# Task2.net
KiCad netlist of a schematic drawn in Altium Designer
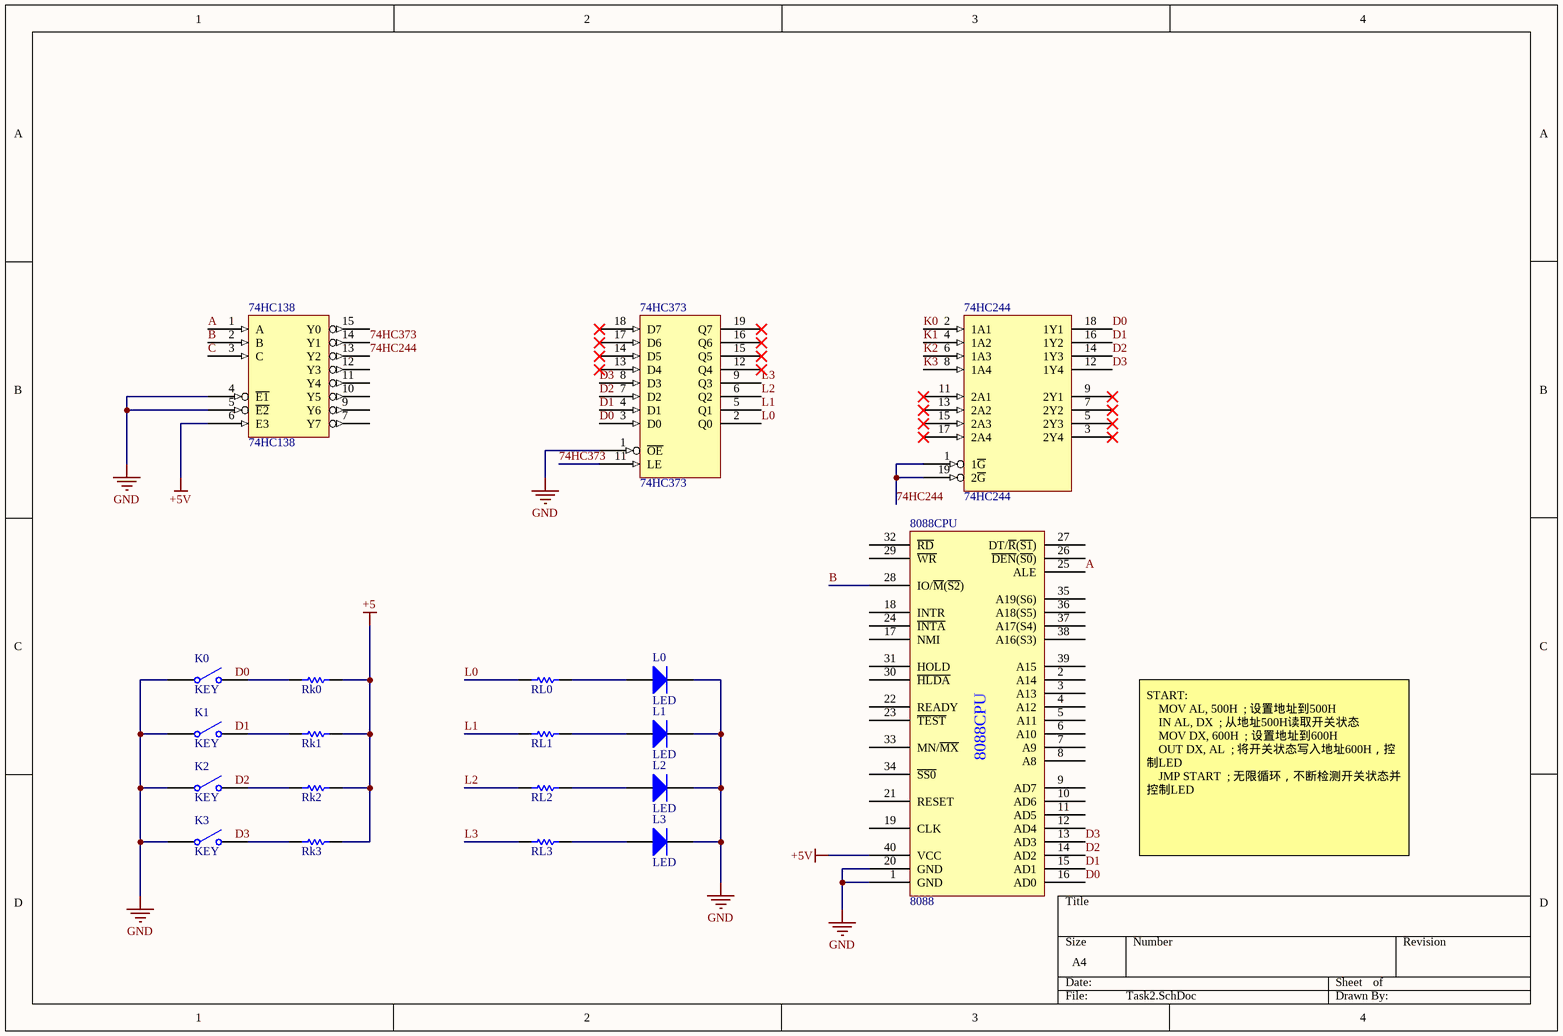
[diagram p0: Task2.SchDoc]

(export (version "E")
  (design (tool "Eeschema 10.0.6"))
  (components
    (comp (ref "74HC138") (value "74HC138") (libsource (lib "BusAndInterfaceDesign") (part "74HC138")))
    (comp (ref "74HC244") (value "74HC244") (libsource (lib "BusAndInterfaceDesign") (part "74HC244")))
    (comp (ref "74HC373") (value "74HC373") (libsource (lib "BusAndInterfaceDesign") (part "74HC373")))
    (comp (ref "8088CPU") (value "8088") (libsource (lib "BusAndInterfaceDesign") (part "8088")))
    (comp (ref "K0") (value "KEY") (libsource (lib "BusAndInterfaceDesign") (part "KEY")))
    (comp (ref "K1") (value "KEY") (libsource (lib "BusAndInterfaceDesign") (part "KEY")))
    (comp (ref "K2") (value "KEY") (libsource (lib "BusAndInterfaceDesign") (part "KEY")))
    (comp (ref "K3") (value "KEY") (libsource (lib "BusAndInterfaceDesign") (part "KEY")))
    (comp (ref "L0") (value "LED") (libsource (lib "BusAndInterfaceDesign") (part "LED")))
    (comp (ref "L1") (value "LED") (libsource (lib "BusAndInterfaceDesign") (part "LED")))
    (comp (ref "L2") (value "LED") (libsource (lib "BusAndInterfaceDesign") (part "LED")))
    (comp (ref "L3") (value "LED") (libsource (lib "BusAndInterfaceDesign") (part "LED")))
    (comp (ref "Rk0") (value "Res") (libsource (lib "BusAndInterfaceDesign") (part "Res")))
    (comp (ref "Rk1") (value "Res") (libsource (lib "BusAndInterfaceDesign") (part "Res")))
    (comp (ref "Rk2") (value "Res") (libsource (lib "BusAndInterfaceDesign") (part "Res")))
    (comp (ref "Rk3") (value "Res") (libsource (lib "BusAndInterfaceDesign") (part "Res")))
    (comp (ref "RL0") (value "Res") (libsource (lib "BusAndInterfaceDesign") (part "Res")))
    (comp (ref "RL1") (value "Res") (libsource (lib "BusAndInterfaceDesign") (part "Res")))
    (comp (ref "RL2") (value "Res") (libsource (lib "BusAndInterfaceDesign") (part "Res")))
    (comp (ref "RL3") (value "Res") (libsource (lib "BusAndInterfaceDesign") (part "Res")))
  )
  (nets
    (net (code "1") (name "+5") (class "Default")
      (node (ref "Rk0") (pin "2") (pinfunction "2_2") (pintype "passive"))
      (node (ref "Rk1") (pin "2") (pinfunction "2_2") (pintype "passive"))
      (node (ref "Rk2") (pin "2") (pinfunction "2_2") (pintype "passive"))
      (node (ref "Rk3") (pin "2") (pinfunction "2_2") (pintype "passive"))
    )
    (net (code "2") (name "+5V") (class "Default")
      (node (ref "74HC138") (pin "6") (pinfunction "E3_6") (pintype "input"))
      (node (ref "8088CPU") (pin "40") (pinfunction "VCC_40") (pintype "passive"))
    )
    (net (code "3") (name "/74HC244") (class "Default")
      (node (ref "74HC138") (pin "13") (pinfunction "Y2_13") (pintype "output"))
      (node (ref "74HC244") (pin "1") (pinfunction "1~{G}_1") (pintype "input"))
      (node (ref "74HC244") (pin "19") (pinfunction "2~{G}_19") (pintype "input"))
    )
    (net (code "4") (name "/74HC373") (class "Default")
      (node (ref "74HC138") (pin "14") (pinfunction "Y1_14") (pintype "output"))
      (node (ref "74HC373") (pin "11") (pinfunction "LE_11") (pintype "input"))
    )
    (net (code "5") (name "/A") (class "Default")
      (node (ref "74HC138") (pin "1") (pinfunction "A_1") (pintype "input"))
      (node (ref "8088CPU") (pin "25") (pinfunction "ALE_25") (pintype "passive"))
    )
    (net (code "6") (name "/B") (class "Default")
      (node (ref "74HC138") (pin "2") (pinfunction "B_2") (pintype "input"))
      (node (ref "8088CPU") (pin "28") (pinfunction "IO/~{M}(~{S2})_28") (pintype "passive"))
    )
    (net (code "7") (name "/C") (class "Default")
      (node (ref "74HC138") (pin "3") (pinfunction "C_3") (pintype "input"))
    )
    (net (code "8") (name "/D0") (class "Default")
      (node (ref "74HC244") (pin "18") (pinfunction "1Y1_18") (pintype "tri_state"))
      (node (ref "74HC373") (pin "3") (pinfunction "D0_3") (pintype "input"))
      (node (ref "8088CPU") (pin "16") (pinfunction "AD0_16") (pintype "passive"))
    )
    (net (code "9") (name "/D1") (class "Default")
      (node (ref "74HC244") (pin "16") (pinfunction "1Y2_16") (pintype "tri_state"))
      (node (ref "74HC373") (pin "4") (pinfunction "D1_4") (pintype "input"))
      (node (ref "8088CPU") (pin "15") (pinfunction "AD1_15") (pintype "passive"))
    )
    (net (code "10") (name "/D2") (class "Default")
      (node (ref "74HC244") (pin "14") (pinfunction "1Y3_14") (pintype "tri_state"))
      (node (ref "74HC373") (pin "7") (pinfunction "D2_7") (pintype "input"))
      (node (ref "8088CPU") (pin "14") (pinfunction "AD2_14") (pintype "passive"))
    )
    (net (code "11") (name "/D3") (class "Default")
      (node (ref "74HC244") (pin "12") (pinfunction "1Y4_12") (pintype "tri_state"))
      (node (ref "74HC373") (pin "8") (pinfunction "D3_8") (pintype "input"))
      (node (ref "8088CPU") (pin "13") (pinfunction "AD3_13") (pintype "passive"))
    )
    (net (code "12") (name "/K0") (class "Default")
      (node (ref "74HC244") (pin "2") (pinfunction "1A1_2") (pintype "input"))
    )
    (net (code "13") (name "/K1") (class "Default")
      (node (ref "74HC244") (pin "4") (pinfunction "1A2_4") (pintype "input"))
    )
    (net (code "14") (name "/K2") (class "Default")
      (node (ref "74HC244") (pin "6") (pinfunction "1A3_6") (pintype "input"))
    )
    (net (code "15") (name "/K3") (class "Default")
      (node (ref "74HC244") (pin "8") (pinfunction "1A4_8") (pintype "input"))
    )
    (net (code "16") (name "/L0") (class "Default")
      (node (ref "74HC373") (pin "2") (pinfunction "Q0_2") (pintype "tri_state"))
      (node (ref "RL0") (pin "1") (pinfunction "1_1") (pintype "passive"))
    )
    (net (code "17") (name "/L1") (class "Default")
      (node (ref "74HC373") (pin "5") (pinfunction "Q1_5") (pintype "tri_state"))
      (node (ref "RL1") (pin "1") (pinfunction "1_1") (pintype "passive"))
    )
    (net (code "18") (name "/L2") (class "Default")
      (node (ref "74HC373") (pin "6") (pinfunction "Q2_6") (pintype "tri_state"))
      (node (ref "RL2") (pin "1") (pinfunction "1_1") (pintype "passive"))
    )
    (net (code "19") (name "/L3") (class "Default")
      (node (ref "74HC373") (pin "9") (pinfunction "Q3_9") (pintype "tri_state"))
      (node (ref "RL3") (pin "1") (pinfunction "1_1") (pintype "passive"))
    )
    (net (code "20") (name "GND") (class "Default")
      (node (ref "74HC138") (pin "4") (pinfunction "~{E1}_4") (pintype "input"))
      (node (ref "74HC138") (pin "5") (pinfunction "~{E2}_5") (pintype "input"))
      (node (ref "74HC373") (pin "1") (pinfunction "~{OE}_1") (pintype "input"))
      (node (ref "8088CPU") (pin "1") (pinfunction "GND_1") (pintype "passive"))
      (node (ref "8088CPU") (pin "20") (pinfunction "GND_20") (pintype "passive"))
      (node (ref "K0") (pin "1") (pinfunction "COMMON_1") (pintype "passive"))
      (node (ref "K1") (pin "1") (pinfunction "COMMON_1") (pintype "passive"))
      (node (ref "K2") (pin "1") (pinfunction "COMMON_1") (pintype "passive"))
      (node (ref "K3") (pin "1") (pinfunction "COMMON_1") (pintype "passive"))
      (node (ref "L0") (pin "2") (pinfunction "K_2") (pintype "passive"))
      (node (ref "L1") (pin "2") (pinfunction "K_2") (pintype "passive"))
      (node (ref "L2") (pin "2") (pinfunction "K_2") (pintype "passive"))
      (node (ref "L3") (pin "2") (pinfunction "K_2") (pintype "passive"))
    )
    (net (code "21") (name "Net-(K0-NO)") (class "Default")
      (node (ref "K0") (pin "2") (pinfunction "NO_2") (pintype "passive"))
      (node (ref "Rk0") (pin "1") (pinfunction "1_1") (pintype "passive"))
    )
    (net (code "22") (name "Net-(K1-NO)") (class "Default")
      (node (ref "K1") (pin "2") (pinfunction "NO_2") (pintype "passive"))
      (node (ref "Rk1") (pin "1") (pinfunction "1_1") (pintype "passive"))
    )
    (net (code "23") (name "Net-(K2-NO)") (class "Default")
      (node (ref "K2") (pin "2") (pinfunction "NO_2") (pintype "passive"))
      (node (ref "Rk2") (pin "1") (pinfunction "1_1") (pintype "passive"))
    )
    (net (code "24") (name "Net-(K3-NO)") (class "Default")
      (node (ref "K3") (pin "2") (pinfunction "NO_2") (pintype "passive"))
      (node (ref "Rk3") (pin "1") (pinfunction "1_1") (pintype "passive"))
    )
    (net (code "25") (name "Net-(L0-A)") (class "Default")
      (node (ref "L0") (pin "1") (pinfunction "A_1") (pintype "passive"))
      (node (ref "RL0") (pin "2") (pinfunction "2_2") (pintype "passive"))
    )
    (net (code "26") (name "Net-(L1-A)") (class "Default")
      (node (ref "L1") (pin "1") (pinfunction "A_1") (pintype "passive"))
      (node (ref "RL1") (pin "2") (pinfunction "2_2") (pintype "passive"))
    )
    (net (code "27") (name "Net-(L2-A)") (class "Default")
      (node (ref "L2") (pin "1") (pinfunction "A_1") (pintype "passive"))
      (node (ref "RL2") (pin "2") (pinfunction "2_2") (pintype "passive"))
    )
    (net (code "28") (name "Net-(L3-A)") (class "Default")
      (node (ref "L3") (pin "1") (pinfunction "A_1") (pintype "passive"))
      (node (ref "RL3") (pin "2") (pinfunction "2_2") (pintype "passive"))
    )
    (net (code "29") (name "unconnected-(74HC138-Y0-Pad15)") (class "Default")
      (node (ref "74HC138") (pin "15") (pinfunction "Y0_15") (pintype "output"))
    )
    (net (code "30") (name "unconnected-(74HC138-Y3-Pad12)") (class "Default")
      (node (ref "74HC138") (pin "12") (pinfunction "Y3_12") (pintype "output"))
    )
    (net (code "31") (name "unconnected-(74HC138-Y4-Pad11)") (class "Default")
      (node (ref "74HC138") (pin "11") (pinfunction "Y4_11") (pintype "output"))
    )
    (net (code "32") (name "unconnected-(74HC138-Y5-Pad10)") (class "Default")
      (node (ref "74HC138") (pin "10") (pinfunction "Y5_10") (pintype "output"))
    )
    (net (code "33") (name "unconnected-(74HC138-Y6-Pad9)") (class "Default")
      (node (ref "74HC138") (pin "9") (pinfunction "Y6_9") (pintype "output"))
    )
    (net (code "34") (name "unconnected-(74HC138-Y7-Pad7)") (class "Default")
      (node (ref "74HC138") (pin "7") (pinfunction "Y7_7") (pintype "output"))
    )
    (net (code "35") (name "unconnected-(74HC244-2A1-Pad11)") (class "Default")
      (node (ref "74HC244") (pin "11") (pinfunction "2A1_11") (pintype "input+no_connect"))
    )
    (net (code "36") (name "unconnected-(74HC244-2A2-Pad13)") (class "Default")
      (node (ref "74HC244") (pin "13") (pinfunction "2A2_13") (pintype "input+no_connect"))
    )
    (net (code "37") (name "unconnected-(74HC244-2A3-Pad15)") (class "Default")
      (node (ref "74HC244") (pin "15") (pinfunction "2A3_15") (pintype "input+no_connect"))
    )
    (net (code "38") (name "unconnected-(74HC244-2A4-Pad17)") (class "Default")
      (node (ref "74HC244") (pin "17") (pinfunction "2A4_17") (pintype "input+no_connect"))
    )
    (net (code "39") (name "unconnected-(74HC244-2Y1-Pad9)") (class "Default")
      (node (ref "74HC244") (pin "9") (pinfunction "2Y1_9") (pintype "tri_state+no_connect"))
    )
    (net (code "40") (name "unconnected-(74HC244-2Y2-Pad7)") (class "Default")
      (node (ref "74HC244") (pin "7") (pinfunction "2Y2_7") (pintype "tri_state+no_connect"))
    )
    (net (code "41") (name "unconnected-(74HC244-2Y3-Pad5)") (class "Default")
      (node (ref "74HC244") (pin "5") (pinfunction "2Y3_5") (pintype "tri_state+no_connect"))
    )
    (net (code "42") (name "unconnected-(74HC244-2Y4-Pad3)") (class "Default")
      (node (ref "74HC244") (pin "3") (pinfunction "2Y4_3") (pintype "tri_state+no_connect"))
    )
    (net (code "43") (name "unconnected-(74HC373-D4-Pad13)") (class "Default")
      (node (ref "74HC373") (pin "13") (pinfunction "D4_13") (pintype "input+no_connect"))
    )
    (net (code "44") (name "unconnected-(74HC373-D5-Pad14)") (class "Default")
      (node (ref "74HC373") (pin "14") (pinfunction "D5_14") (pintype "input+no_connect"))
    )
    (net (code "45") (name "unconnected-(74HC373-D6-Pad17)") (class "Default")
      (node (ref "74HC373") (pin "17") (pinfunction "D6_17") (pintype "input+no_connect"))
    )
    (net (code "46") (name "unconnected-(74HC373-D7-Pad18)") (class "Default")
      (node (ref "74HC373") (pin "18") (pinfunction "D7_18") (pintype "input+no_connect"))
    )
    (net (code "47") (name "unconnected-(74HC373-Q4-Pad12)") (class "Default")
      (node (ref "74HC373") (pin "12") (pinfunction "Q4_12") (pintype "tri_state+no_connect"))
    )
    (net (code "48") (name "unconnected-(74HC373-Q5-Pad15)") (class "Default")
      (node (ref "74HC373") (pin "15") (pinfunction "Q5_15") (pintype "tri_state+no_connect"))
    )
    (net (code "49") (name "unconnected-(74HC373-Q6-Pad16)") (class "Default")
      (node (ref "74HC373") (pin "16") (pinfunction "Q6_16") (pintype "tri_state+no_connect"))
    )
    (net (code "50") (name "unconnected-(74HC373-Q7-Pad19)") (class "Default")
      (node (ref "74HC373") (pin "19") (pinfunction "Q7_19") (pintype "tri_state+no_connect"))
    )
    (net (code "51") (name "unconnected-(8088CPU-A8-Pad8)") (class "Default")
      (node (ref "8088CPU") (pin "8") (pinfunction "A8_8") (pintype "passive"))
    )
    (net (code "52") (name "unconnected-(8088CPU-A9-Pad7)") (class "Default")
      (node (ref "8088CPU") (pin "7") (pinfunction "A9_7") (pintype "passive"))
    )
    (net (code "53") (name "unconnected-(8088CPU-A10-Pad6)") (class "Default")
      (node (ref "8088CPU") (pin "6") (pinfunction "A10_6") (pintype "passive"))
    )
    (net (code "54") (name "unconnected-(8088CPU-A11-Pad5)") (class "Default")
      (node (ref "8088CPU") (pin "5") (pinfunction "A11_5") (pintype "passive"))
    )
    (net (code "55") (name "unconnected-(8088CPU-A12-Pad4)") (class "Default")
      (node (ref "8088CPU") (pin "4") (pinfunction "A12_4") (pintype "passive"))
    )
    (net (code "56") (name "unconnected-(8088CPU-A13-Pad3)") (class "Default")
      (node (ref "8088CPU") (pin "3") (pinfunction "A13_3") (pintype "passive"))
    )
    (net (code "57") (name "unconnected-(8088CPU-A14-Pad2)") (class "Default")
      (node (ref "8088CPU") (pin "2") (pinfunction "A14_2") (pintype "passive"))
    )
    (net (code "58") (name "unconnected-(8088CPU-A15-Pad39)") (class "Default")
      (node (ref "8088CPU") (pin "39") (pinfunction "A15_39") (pintype "passive"))
    )
    (net (code "59") (name "unconnected-(8088CPU-A16(S3)-Pad38)") (class "Default")
      (node (ref "8088CPU") (pin "38") (pinfunction "A16(S3)_38") (pintype "passive"))
    )
    (net (code "60") (name "unconnected-(8088CPU-A17(S4)-Pad37)") (class "Default")
      (node (ref "8088CPU") (pin "37") (pinfunction "A17(S4)_37") (pintype "passive"))
    )
    (net (code "61") (name "unconnected-(8088CPU-A18(S5)-Pad36)") (class "Default")
      (node (ref "8088CPU") (pin "36") (pinfunction "A18(S5)_36") (pintype "passive"))
    )
    (net (code "62") (name "unconnected-(8088CPU-A19(S6)-Pad35)") (class "Default")
      (node (ref "8088CPU") (pin "35") (pinfunction "A19(S6)_35") (pintype "passive"))
    )
    (net (code "63") (name "unconnected-(8088CPU-AD4-Pad12)") (class "Default")
      (node (ref "8088CPU") (pin "12") (pinfunction "AD4_12") (pintype "passive"))
    )
    (net (code "64") (name "unconnected-(8088CPU-AD5-Pad11)") (class "Default")
      (node (ref "8088CPU") (pin "11") (pinfunction "AD5_11") (pintype "passive"))
    )
    (net (code "65") (name "unconnected-(8088CPU-AD6-Pad10)") (class "Default")
      (node (ref "8088CPU") (pin "10") (pinfunction "AD6_10") (pintype "passive"))
    )
    (net (code "66") (name "unconnected-(8088CPU-AD7-Pad9)") (class "Default")
      (node (ref "8088CPU") (pin "9") (pinfunction "AD7_9") (pintype "passive"))
    )
    (net (code "67") (name "unconnected-(8088CPU-CLK-Pad19)") (class "Default")
      (node (ref "8088CPU") (pin "19") (pinfunction "CLK_19") (pintype "passive"))
    )
    (net (code "68") (name "unconnected-(8088CPU-DT{slash}~{R}(~{S1})-Pad27)") (class "Default")
      (node (ref "8088CPU") (pin "27") (pinfunction "DT/~{R}(~{S1})_27") (pintype "passive"))
    )
    (net (code "69") (name "unconnected-(8088CPU-HOLD-Pad31)") (class "Default")
      (node (ref "8088CPU") (pin "31") (pinfunction "HOLD_31") (pintype "passive"))
    )
    (net (code "70") (name "unconnected-(8088CPU-INTR-Pad18)") (class "Default")
      (node (ref "8088CPU") (pin "18") (pinfunction "INTR_18") (pintype "passive"))
    )
    (net (code "71") (name "unconnected-(8088CPU-MN{slash}~{MX}-Pad33)") (class "Default")
      (node (ref "8088CPU") (pin "33") (pinfunction "MN/~{MX}_33") (pintype "passive"))
    )
    (net (code "72") (name "unconnected-(8088CPU-NMI-Pad17)") (class "Default")
      (node (ref "8088CPU") (pin "17") (pinfunction "NMI_17") (pintype "passive"))
    )
    (net (code "73") (name "unconnected-(8088CPU-READY-Pad22)") (class "Default")
      (node (ref "8088CPU") (pin "22") (pinfunction "READY_22") (pintype "passive"))
    )
    (net (code "74") (name "unconnected-(8088CPU-RESET-Pad21)") (class "Default")
      (node (ref "8088CPU") (pin "21") (pinfunction "RESET_21") (pintype "passive"))
    )
    (net (code "75") (name "unconnected-(8088CPU-~{DEN}(~{S0})-Pad26)") (class "Default")
      (node (ref "8088CPU") (pin "26") (pinfunction "~{DEN}(~{S0})_26") (pintype "passive"))
    )
    (net (code "76") (name "unconnected-(8088CPU-~{HLDA}-Pad30)") (class "Default")
      (node (ref "8088CPU") (pin "30") (pinfunction "~{HLDA}_30") (pintype "passive"))
    )
    (net (code "77") (name "unconnected-(8088CPU-~{INTA}-Pad24)") (class "Default")
      (node (ref "8088CPU") (pin "24") (pinfunction "~{INTA}_24") (pintype "passive"))
    )
    (net (code "78") (name "unconnected-(8088CPU-~{RD}-Pad32)") (class "Default")
      (node (ref "8088CPU") (pin "32") (pinfunction "~{RD}_32") (pintype "passive"))
    )
    (net (code "79") (name "unconnected-(8088CPU-~{SS0}-Pad34)") (class "Default")
      (node (ref "8088CPU") (pin "34") (pinfunction "~{SS0}_34") (pintype "passive"))
    )
    (net (code "80") (name "unconnected-(8088CPU-~{TEST}-Pad23)") (class "Default")
      (node (ref "8088CPU") (pin "23") (pinfunction "~{TEST}_23") (pintype "passive"))
    )
    (net (code "81") (name "unconnected-(8088CPU-~{WR}-Pad29)") (class "Default")
      (node (ref "8088CPU") (pin "29") (pinfunction "~{WR}_29") (pintype "passive"))
    )
  )
)
